# cuk.net
KiCad netlist of a schematic drawn in Altium Designer
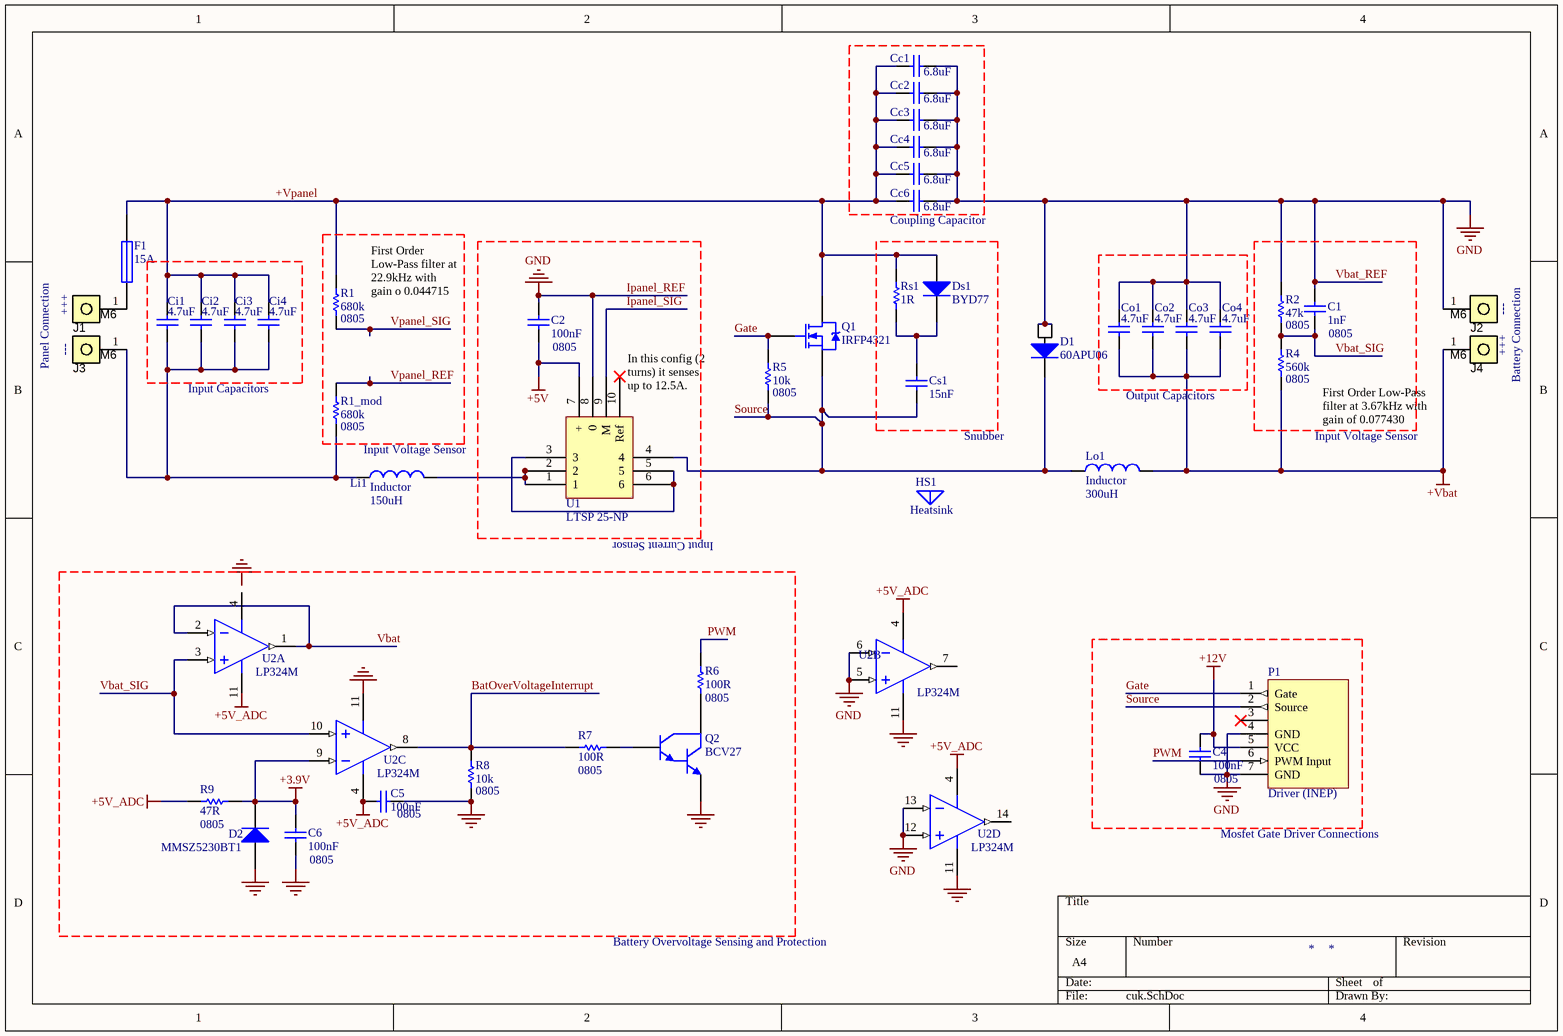
[diagram p0: cuk.SchDoc]

(export (version "E")
  (design (tool "Eeschema 10.0.6"))
  (components
    (comp (ref "C1")
      (value "1nF")
      (footprint "0805")
      (description "Capacitor")
      (libsource (lib "Miscellaneous Devices") (part "Cap"))
    )
    (comp (ref "C2")
      (value "100nF")
      (footprint "0805")
      (description "Capacitor")
      (libsource (lib "Miscellaneous Devices") (part "Cap"))
    )
    (comp (ref "C4")
      (value "100nF")
      (footprint "0805")
      (description "Capacitor")
      (libsource (lib "Miscellaneous Devices") (part "Cap"))
    )
    (comp (ref "C5")
      (value "100nF")
      (footprint "0805")
      (description "Capacitor")
      (libsource (lib "Miscellaneous Devices") (part "Cap"))
    )
    (comp (ref "C6")
      (value "100nF")
      (footprint "0805")
      (description "Capacitor")
      (libsource (lib "Miscellaneous Devices") (part "Cap"))
    )
    (comp (ref "Cc1")
      (value "6.8uF")
      (footprint "CAP4U7 EPCOS")
      (description "Capacitor")
      (fields (field (name "VOLTAGE") "250V") (field (name "Comment") "Cap"))
      (libsource (lib "Miscellaneous Devices") (part "Cap"))
    )
    (comp (ref "Cc2")
      (value "6.8uF")
      (footprint "CAP4U7 EPCOS")
      (description "Capacitor")
      (fields (field (name "VOLTAGE") "250V") (field (name "Comment") "Cap"))
      (libsource (lib "Miscellaneous Devices") (part "Cap"))
    )
    (comp (ref "Cc3")
      (value "6.8uF")
      (footprint "CAP4U7 EPCOS")
      (description "Capacitor")
      (fields (field (name "VOLTAGE") "250V") (field (name "Comment") "Cap"))
      (libsource (lib "Miscellaneous Devices") (part "Cap"))
    )
    (comp (ref "Cc4")
      (value "6.8uF")
      (footprint "CAP4U7 EPCOS")
      (description "Capacitor")
      (fields (field (name "VOLTAGE") "250V") (field (name "Comment") "Cap"))
      (libsource (lib "Miscellaneous Devices") (part "Cap"))
    )
    (comp (ref "Cc5")
      (value "6.8uF")
      (footprint "CAP4U7 EPCOS")
      (description "Capacitor")
      (fields (field (name "VOLTAGE") "250V") (field (name "Comment") "Cap"))
      (libsource (lib "Miscellaneous Devices") (part "Cap"))
    )
    (comp (ref "Cc6")
      (value "6.8uF")
      (footprint "CAP4U7 EPCOS")
      (description "Capacitor")
      (fields (field (name "VOLTAGE") "250V") (field (name "Comment") "Cap"))
      (libsource (lib "Miscellaneous Devices") (part "Cap"))
    )
    (comp (ref "Ci1")
      (value "4.7uF")
      (footprint "cap4u7")
      (description "Capacitor")
      (fields (field (name "VOLTAGE") "100V") (field (name "Comment") "Cap"))
      (libsource (lib "Miscellaneous Devices") (part "Cap"))
    )
    (comp (ref "Ci2")
      (value "4.7uF")
      (footprint "cap4u7")
      (description "Capacitor")
      (fields (field (name "VOLTAGE") "100V") (field (name "Comment") "Cap"))
      (libsource (lib "Miscellaneous Devices") (part "Cap"))
    )
    (comp (ref "Ci3")
      (value "4.7uF")
      (footprint "cap4u7")
      (description "Capacitor")
      (fields (field (name "VOLTAGE") "100V") (field (name "Comment") "Cap"))
      (libsource (lib "Miscellaneous Devices") (part "Cap"))
    )
    (comp (ref "Ci4")
      (value "4.7uF")
      (footprint "cap4u7")
      (description "Capacitor")
      (fields (field (name "VOLTAGE") "100V") (field (name "Comment") "Cap"))
      (libsource (lib "Miscellaneous Devices") (part "Cap"))
    )
    (comp (ref "Co1")
      (value "4.7uF")
      (footprint "CAP4U7 EPCOS")
      (description "Capacitor")
      (fields (field (name "VOLTAGE") "250V"))
      (libsource (lib "Miscellaneous Devices") (part "Cap"))
    )
    (comp (ref "Co2")
      (value "4.7uF")
      (footprint "CAP4U7 EPCOS")
      (description "Capacitor")
      (fields (field (name "VOLTAGE") "250V"))
      (libsource (lib "Miscellaneous Devices") (part "Cap"))
    )
    (comp (ref "Co3")
      (value "4.7uF")
      (footprint "CAP4U7 EPCOS")
      (description "Capacitor")
      (fields (field (name "VOLTAGE") "250V"))
      (libsource (lib "Miscellaneous Devices") (part "Cap"))
    )
    (comp (ref "Co4")
      (value "4.7uF")
      (footprint "CAP4U7 EPCOS")
      (description "Capacitor")
      (fields (field (name "VOLTAGE") "250V"))
      (libsource (lib "Miscellaneous Devices") (part "Cap"))
    )
    (comp (ref "Cs1")
      (value "15nF")
      (footprint "100nF")
      (description "Capacitor")
      (libsource (lib "Miscellaneous Devices") (part "Cap"))
    )
    (comp (ref "D1")
      (value "60APU06")
      (footprint "to-247ac_horizontal")
      (libsource (lib "ControladorCarga") (part "60APU06"))
    )
    (comp (ref "D2")
      (value "MMSZ5230BT1")
      (footprint "DSO-C2/X3.3")
      (description "Zener smd 3.9V")
      (libsource (lib "Miscellaneous Devices") (part "Diode"))
    )
    (comp (ref "Ds1")
      (value "BYD77")
      (footprint "DSO-C2/X2.3")
      (description "1 Amp General Purpose Rectifier")
      (libsource (lib "Miscellaneous Devices") (part "Diode 1N4002"))
    )
    (comp (ref "F1")
      (value "15A")
      (footprint "Porta Fusivel")
      (description "Fuse 5x20")
      (libsource (lib "Miscellaneous Devices") (part "Fuse 1"))
    )
    (comp (ref "HS1")
      (value "Heatsink")
      (footprint "HS10425")
      (description "Generic Antenna")
      (libsource (lib "Miscellaneous Devices") (part "Antenna"))
    )
    (comp (ref "J1")
      (value "M6")
      (footprint "Parafuso")
      (description "+++")
      (libsource (lib "") (part "CONN_1_BIG_1"))
    )
    (comp (ref "J2")
      (value "M6")
      (footprint "Parafuso")
      (description "---")
      (libsource (lib "DatabaseAltium") (part "CONN_1_BIG"))
    )
    (comp (ref "J3")
      (value "M6")
      (footprint "Parafuso")
      (description "---")
      (libsource (lib "") (part "CONN_1_BIG_1"))
    )
    (comp (ref "J4")
      (value "M6")
      (footprint "Parafuso")
      (description "+++")
      (libsource (lib "DatabaseAltium") (part "CONN_1_BIG"))
    )
    (comp (ref "Li1")
      (value "Inductor")
      (footprint "NEE-42-20-DEITADO")
      (fields (field (name "ALTIUM_VALUE") "150uH"))
      (libsource (lib "Miscellaneous Devices") (part "Inductor"))
    )
    (comp (ref "Lo1")
      (value "Inductor")
      (footprint "NEE-42-20-DEITADO")
      (fields (field (name "ALTIUM_VALUE") "300uH"))
      (libsource (lib "Miscellaneous Devices") (part "Inductor"))
    )
    (comp (ref "P1")
      (value "Driver (INEP)")
      (footprint "Driver INEP")
      (description "Driver INEP (Soeiro)")
      (libsource (lib "ControladorCarga") (part "Driver_INEP"))
    )
    (comp (ref "Q1")
      (value "IRFP4321")
      (footprint "to-247ac_horizontal")
      (description "HEXFET Power MOSFET")
      (libsource (lib "IR Discrete MOSFET - Power") (part "IRFP260"))
    )
    (comp (ref "Q2")
      (value "BCV27")
      (footprint "SOT95P240-3N")
      (description "NPN Darlington Bipolar Transistor")
      (libsource (lib "Miscellaneous Devices") (part "NPN1"))
    )
    (comp (ref "R1")
      (value "680k")
      (footprint "0805R")
      (description "Resistor")
      (fields (field (name "TYPE") "0805"))
      (libsource (lib "Miscellaneous Devices") (part "Res1"))
    )
    (comp (ref "R1_mod")
      (value "680k")
      (footprint "0805R")
      (description "Resistor")
      (fields (field (name "TYPE") "0805"))
      (libsource (lib "Miscellaneous Devices") (part "Res1"))
    )
    (comp (ref "R2")
      (value "47k")
      (footprint "0805R")
      (description "Resistor")
      (fields (field (name "TYPE") "0805"))
      (libsource (lib "Miscellaneous Devices") (part "Res1"))
    )
    (comp (ref "R4")
      (value "560k")
      (footprint "0805R")
      (description "Resistor")
      (fields (field (name "TYPE") "0805"))
      (libsource (lib "Miscellaneous Devices") (part "Res1"))
    )
    (comp (ref "R5")
      (value "10k")
      (footprint "0805R")
      (description "Resistor")
      (fields (field (name "TYPE") "0805"))
      (libsource (lib "Miscellaneous Devices") (part "Res1"))
    )
    (comp (ref "R6")
      (value "100R")
      (footprint "0805R")
      (description "Resistor")
      (fields (field (name "TYPE") "0805"))
      (libsource (lib "Miscellaneous Devices") (part "Res1"))
    )
    (comp (ref "R7")
      (value "100R")
      (footprint "0805R")
      (description "Resistor")
      (fields (field (name "TYPE") "0805"))
      (libsource (lib "Miscellaneous Devices") (part "Res1"))
    )
    (comp (ref "R8")
      (value "10k")
      (footprint "0805R")
      (description "Resistor")
      (fields (field (name "TYPE") "0805"))
      (libsource (lib "Miscellaneous Devices") (part "Res1"))
    )
    (comp (ref "R9")
      (value "47R")
      (footprint "0805R")
      (description "Resistor")
      (fields (field (name "TYPE") "0805"))
      (libsource (lib "Miscellaneous Devices") (part "Res1"))
    )
    (comp (ref "Rs1")
      (value "1R")
      (footprint "AXIAL-0.3")
      (description "Resistor")
      (libsource (lib "Miscellaneous Devices") (part "Res1"))
    )
    (comp (ref "U1")
      (value "LTSP 25-NP")
      (footprint "LTSP 25-NP")
      (description "Current Transducer LTSP (25 A)")
      (libsource (lib "ControladorCarga") (part "LTSP 25-NP"))
    )
    (comp (ref "U2")
      (value "LP324M")
      (footprint "SOIC14-150(50)")
      (description "Micropower Quad Operational Amplifier")
      (libsource (lib "Lib") (part "LP324M"))
    )
  )
  (nets
    (net (code "1") (name "+3.9V") (class "Default")
      (node (ref "C6") (pin "2") (pinfunction "2_2") (pintype "passive"))
      (node (ref "D2") (pin "2") (pinfunction "K_2") (pintype "passive"))
      (node (ref "R9") (pin "1") (pinfunction "1_1") (pintype "passive"))
      (node (ref "U2") (pin "9") (pinfunction "IN3-_9") (pintype "input"))
    )
    (net (code "2") (name "+5V") (class "Default")
      (node (ref "C2") (pin "1") (pinfunction "1_1") (pintype "passive"))
      (node (ref "U1") (pin "7") (pinfunction "+_7") (pintype "passive"))
    )
    (net (code "3") (name "+5V_ADC") (class "Default")
      (node (ref "C5") (pin "2") (pinfunction "2_2") (pintype "passive"))
      (node (ref "R9") (pin "2") (pinfunction "2_2") (pintype "passive"))
      (node (ref "U2") (pin "4") (pinfunction "V+_4") (pintype "power_in"))
    )
    (net (code "4") (name "+12V") (class "Default")
      (node (ref "C4") (pin "2") (pinfunction "2_2") (pintype "passive"))
      (node (ref "P1") (pin "5") (pinfunction "VCC_5") (pintype "power_in"))
    )
    (net (code "5") (name "+Vbat") (class "Default")
      (node (ref "Co1") (pin "1") (pinfunction "1_1") (pintype "passive"))
      (node (ref "Co2") (pin "1") (pinfunction "1_1") (pintype "passive"))
      (node (ref "Co3") (pin "1") (pinfunction "1_1") (pintype "passive"))
      (node (ref "Co4") (pin "1") (pinfunction "1_1") (pintype "passive"))
      (node (ref "J4") (pin "1") (pinfunction "1_1") (pintype "passive"))
      (node (ref "Lo1") (pin "2") (pinfunction "2_2") (pintype "passive"))
      (node (ref "R4") (pin "1") (pinfunction "1_1") (pintype "passive"))
    )
    (net (code "6") (name "/+Vpanel") (class "Default")
      (node (ref "Cc1") (pin "1") (pinfunction "1_1") (pintype "passive"))
      (node (ref "Cc2") (pin "1") (pinfunction "1_1") (pintype "passive"))
      (node (ref "Cc3") (pin "1") (pinfunction "1_1") (pintype "passive"))
      (node (ref "Cc4") (pin "1") (pinfunction "1_1") (pintype "passive"))
      (node (ref "Cc5") (pin "1") (pinfunction "1_1") (pintype "passive"))
      (node (ref "Cc6") (pin "1") (pinfunction "1_1") (pintype "passive"))
      (node (ref "Ci1") (pin "2") (pinfunction "2_2") (pintype "passive"))
      (node (ref "Ci2") (pin "2") (pinfunction "2_2") (pintype "passive"))
      (node (ref "Ci3") (pin "2") (pinfunction "2_2") (pintype "passive"))
      (node (ref "Ci4") (pin "2") (pinfunction "2_2") (pintype "passive"))
      (node (ref "Ds1") (pin "1") (pinfunction "A_1") (pintype "passive"))
      (node (ref "F1") (pin "1") (pinfunction "1_1") (pintype "passive"))
      (node (ref "Q1") (pin "2") (pinfunction "D_2") (pintype "passive"))
      (node (ref "R1") (pin "2") (pinfunction "2_2") (pintype "passive"))
      (node (ref "Rs1") (pin "2") (pinfunction "2_2") (pintype "passive"))
    )
    (net (code "7") (name "/BatOverVoltageInterrupt") (class "Default")
      (node (ref "R7") (pin "2") (pinfunction "2_2") (pintype "passive"))
      (node (ref "R8") (pin "2") (pinfunction "2_2") (pintype "passive"))
      (node (ref "U2") (pin "8") (pinfunction "OUT3_8") (pintype "output"))
    )
    (net (code "8") (name "/Gate") (class "Default")
      (node (ref "P1") (pin "1") (pinfunction "Gate_1") (pintype "output"))
      (node (ref "Q1") (pin "1") (pinfunction "G_1") (pintype "passive"))
      (node (ref "R5") (pin "2") (pinfunction "2_2") (pintype "passive"))
    )
    (net (code "9") (name "/Ipanel_SIG") (class "Default")
      (node (ref "U1") (pin "9") (pinfunction "M_9") (pintype "passive"))
    )
    (net (code "10") (name "/PWM") (class "Default")
      (node (ref "P1") (pin "6") (pinfunction "PWM_Input_6") (pintype "input"))
      (node (ref "R6") (pin "1") (pinfunction "1_1") (pintype "passive"))
    )
    (net (code "11") (name "/Source") (class "Default")
      (node (ref "Cs1") (pin "1") (pinfunction "1_1") (pintype "passive"))
      (node (ref "D1") (pin "2") (pinfunction "K_2") (pintype "passive"))
      (node (ref "Lo1") (pin "1") (pinfunction "1_1") (pintype "passive"))
      (node (ref "P1") (pin "2") (pinfunction "Source_2") (pintype "output"))
      (node (ref "Q1") (pin "3") (pinfunction "S_3") (pintype "passive"))
      (node (ref "R5") (pin "1") (pinfunction "1_1") (pintype "passive"))
      (node (ref "U1") (pin "4") (pinfunction "4_4") (pintype "passive"))
    )
    (net (code "12") (name "/Vbat") (class "Default")
      (node (ref "U2") (pin "1") (pinfunction "OUT1_1") (pintype "output"))
      (node (ref "U2") (pin "2") (pinfunction "IN1-_2") (pintype "input"))
    )
    (net (code "13") (name "/Vbat_SIG") (class "Default")
      (node (ref "C1") (pin "1") (pinfunction "1_1") (pintype "passive"))
      (node (ref "R2") (pin "1") (pinfunction "1_1") (pintype "passive"))
      (node (ref "R4") (pin "2") (pinfunction "2_2") (pintype "passive"))
      (node (ref "U2") (pin "10") (pinfunction "IN3+_10") (pintype "input"))
      (node (ref "U2") (pin "3") (pinfunction "IN1+_3") (pintype "input"))
    )
    (net (code "14") (name "/Vpanel_REF") (class "Default")
      (node (ref "R1_mod") (pin "2") (pinfunction "2_2") (pintype "passive"))
    )
    (net (code "15") (name "/Vpanel_SIG") (class "Default")
      (node (ref "R1") (pin "1") (pinfunction "1_1") (pintype "passive"))
    )
    (net (code "16") (name "GND") (class "Default")
      (node (ref "C1") (pin "2") (pinfunction "2_2") (pintype "passive"))
      (node (ref "C2") (pin "2") (pinfunction "2_2") (pintype "passive"))
      (node (ref "C4") (pin "1") (pinfunction "1_1") (pintype "passive"))
      (node (ref "C5") (pin "1") (pinfunction "1_1") (pintype "passive"))
      (node (ref "C6") (pin "1") (pinfunction "1_1") (pintype "passive"))
      (node (ref "Cc1") (pin "2") (pinfunction "2_2") (pintype "passive"))
      (node (ref "Cc2") (pin "2") (pinfunction "2_2") (pintype "passive"))
      (node (ref "Cc3") (pin "2") (pinfunction "2_2") (pintype "passive"))
      (node (ref "Cc4") (pin "2") (pinfunction "2_2") (pintype "passive"))
      (node (ref "Cc5") (pin "2") (pinfunction "2_2") (pintype "passive"))
      (node (ref "Cc6") (pin "2") (pinfunction "2_2") (pintype "passive"))
      (node (ref "Co1") (pin "2") (pinfunction "2_2") (pintype "passive"))
      (node (ref "Co2") (pin "2") (pinfunction "2_2") (pintype "passive"))
      (node (ref "Co3") (pin "2") (pinfunction "2_2") (pintype "passive"))
      (node (ref "Co4") (pin "2") (pinfunction "2_2") (pintype "passive"))
      (node (ref "D1") (pin "1") (pinfunction "A_1") (pintype "passive"))
      (node (ref "D1") (pin "3") (pinfunction "A_3") (pintype "passive"))
      (node (ref "D2") (pin "1") (pinfunction "A_1") (pintype "passive"))
      (node (ref "J2") (pin "1") (pinfunction "1_1") (pintype "passive"))
      (node (ref "P1") (pin "4") (pinfunction "GND_4") (pintype "power_in"))
      (node (ref "P1") (pin "7") (pinfunction "GND_7") (pintype "power_in"))
      (node (ref "Q2") (pin "3") (pinfunction "E_3") (pintype "passive"))
      (node (ref "R2") (pin "2") (pinfunction "2_2") (pintype "passive"))
      (node (ref "R8") (pin "1") (pinfunction "1_1") (pintype "passive"))
      (node (ref "U1") (pin "8") (pinfunction "0_8") (pintype "passive"))
      (node (ref "U2") (pin "11") (pinfunction "GND_11") (pintype "power_in"))
      (node (ref "U2") (pin "12") (pinfunction "IN4+_12") (pintype "input"))
      (node (ref "U2") (pin "13") (pinfunction "IN4-_13") (pintype "input"))
      (node (ref "U2") (pin "5") (pinfunction "IN2+_5") (pintype "input"))
      (node (ref "U2") (pin "6") (pinfunction "IN2-_6") (pintype "input"))
    )
    (net (code "17") (name "Net-(Ci1-Pad1)") (class "Default")
      (node (ref "Ci1") (pin "1") (pinfunction "1_1") (pintype "passive"))
      (node (ref "Ci2") (pin "1") (pinfunction "1_1") (pintype "passive"))
      (node (ref "Ci3") (pin "1") (pinfunction "1_1") (pintype "passive"))
      (node (ref "Ci4") (pin "1") (pinfunction "1_1") (pintype "passive"))
      (node (ref "J3") (pin "1") (pinfunction "1_1") (pintype "passive"))
      (node (ref "Li1") (pin "1") (pinfunction "1_1") (pintype "passive"))
      (node (ref "R1_mod") (pin "1") (pinfunction "1_1") (pintype "passive"))
    )
    (net (code "18") (name "Net-(Ds1-K)") (class "Default")
      (node (ref "Cs1") (pin "2") (pinfunction "2_2") (pintype "passive"))
      (node (ref "Ds1") (pin "2") (pinfunction "K_2") (pintype "passive"))
      (node (ref "Rs1") (pin "1") (pinfunction "1_1") (pintype "passive"))
    )
    (net (code "19") (name "Net-(F1-Pad2)") (class "Default")
      (node (ref "F1") (pin "2") (pinfunction "2_2") (pintype "passive"))
      (node (ref "J1") (pin "1") (pinfunction "1_1") (pintype "passive"))
    )
    (net (code "20") (name "Net-(Li1-Pad2)") (class "Default")
      (node (ref "Li1") (pin "2") (pinfunction "2_2") (pintype "passive"))
      (node (ref "U1") (pin "1") (pinfunction "1_1") (pintype "passive"))
      (node (ref "U1") (pin "2") (pinfunction "2_2") (pintype "passive"))
    )
    (net (code "21") (name "Net-(Q2-B)") (class "Default")
      (node (ref "Q2") (pin "2") (pinfunction "B_2") (pintype "passive"))
      (node (ref "R7") (pin "1") (pinfunction "1_1") (pintype "passive"))
    )
    (net (code "22") (name "Net-(Q2-C)") (class "Default")
      (node (ref "Q2") (pin "1") (pinfunction "C_1") (pintype "passive"))
      (node (ref "R6") (pin "2") (pinfunction "2_2") (pintype "passive"))
    )
    (net (code "23") (name "Net-(U1-Pad3)") (class "Default")
      (node (ref "U1") (pin "3") (pinfunction "3_3") (pintype "passive"))
      (node (ref "U1") (pin "5") (pinfunction "5_5") (pintype "passive"))
      (node (ref "U1") (pin "6") (pinfunction "6_6") (pintype "passive"))
    )
    (net (code "24") (name "unconnected-(P1-Pad3)") (class "Default")
      (node (ref "P1") (pin "3") (pintype "tri_state+no_connect"))
    )
    (net (code "25") (name "unconnected-(U1-Ref-Pad10)") (class "Default")
      (node (ref "U1") (pin "10") (pinfunction "Ref_10") (pintype "passive+no_connect"))
    )
    (net (code "26") (name "unconnected-(U2A-GND-Pad11)") (class "Default")
      (node (ref "U2") (pin "11") (pinfunction "GND_11") (pintype "power_in"))
    )
    (net (code "27") (name "unconnected-(U2A-V+-Pad4)") (class "Default")
      (node (ref "U2") (pin "4") (pinfunction "V+_4") (pintype "power_in"))
    )
    (net (code "28") (name "unconnected-(U2B-OUT2-Pad7)") (class "Default")
      (node (ref "U2") (pin "7") (pinfunction "OUT2_7") (pintype "output"))
    )
    (net (code "29") (name "unconnected-(U2D-OUT4-Pad14)") (class "Default")
      (node (ref "U2") (pin "14") (pinfunction "OUT4_14") (pintype "output"))
    )
  )
)
